# CDCEmu_Analog.net
KiCad netlist of a schematic drawn in EAGLE
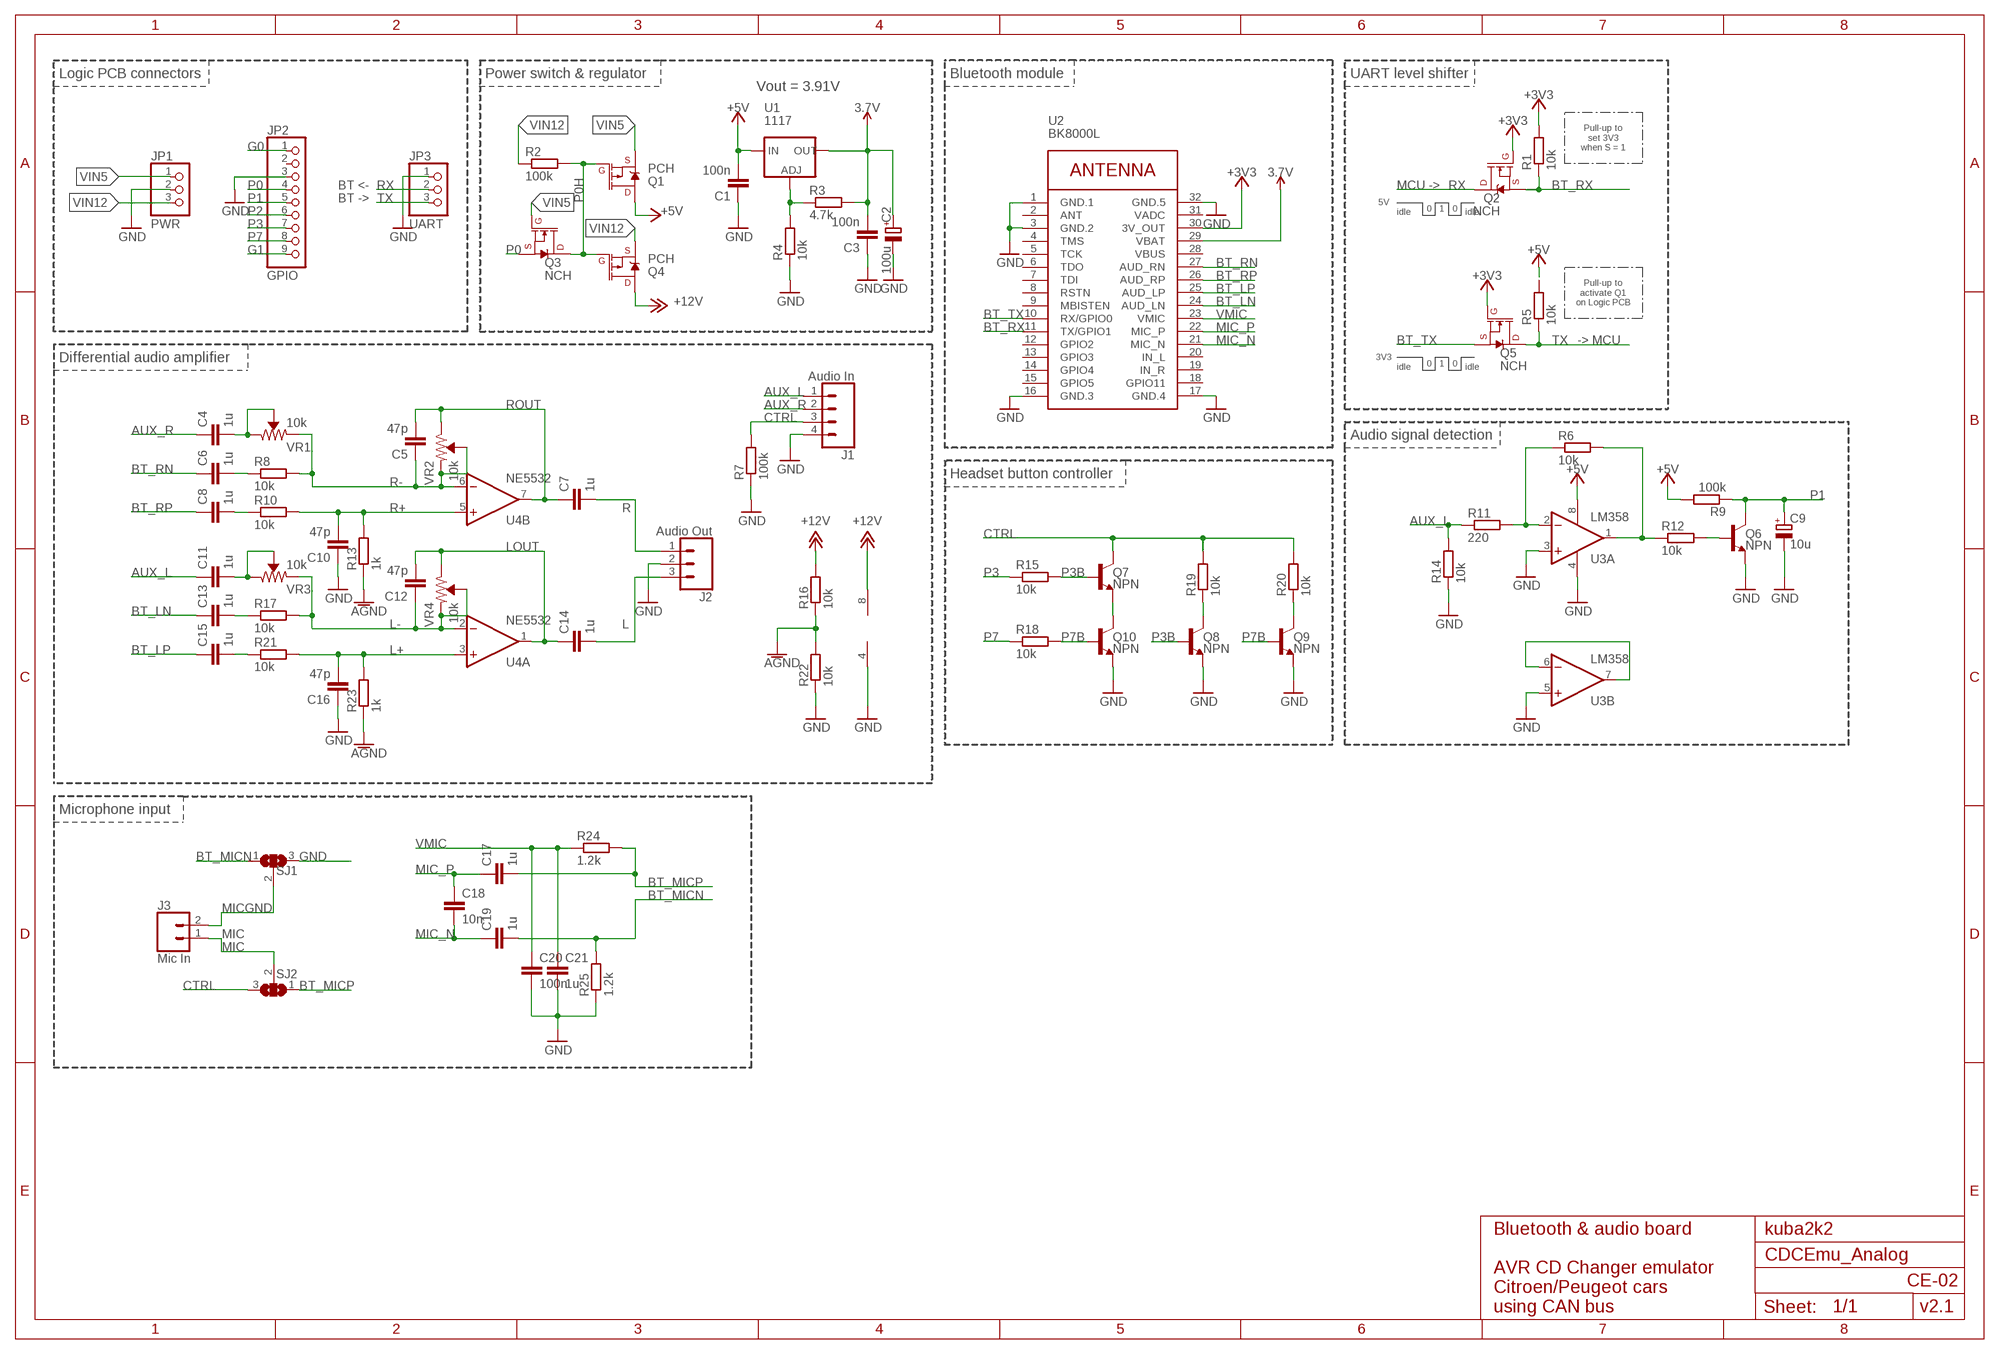
[diagram p0: schematic, sheet 1]

(export (version "E")
  (design (tool "Eeschema 10.0.6"))
  (components
    (comp (ref "C1")
      (value "100n")
      (footprint "eagle-import:C0805")
      (libsource (lib "eagle-import") (part "C-EUC0805"))
    )
    (comp (ref "C2")
      (value "100u")
      (footprint "eagle-import:SMC_B")
      (libsource (lib "eagle-import") (part "CPOL-EUSMCB"))
    )
    (comp (ref "C3")
      (value "100n")
      (footprint "eagle-import:C0805")
      (libsource (lib "eagle-import") (part "C-EUC0805"))
    )
    (comp (ref "C4")
      (value "1u")
      (footprint "eagle-import:C0805")
      (libsource (lib "eagle-import") (part "C-EUC0805"))
    )
    (comp (ref "C5")
      (value "47p")
      (footprint "eagle-import:C0805")
      (libsource (lib "eagle-import") (part "C-EUC0805"))
    )
    (comp (ref "C6")
      (value "1u")
      (footprint "eagle-import:C0805")
      (libsource (lib "eagle-import") (part "C-EUC0805"))
    )
    (comp (ref "C7")
      (value "1u")
      (footprint "eagle-import:C0805")
      (libsource (lib "eagle-import") (part "C-EUC0805"))
    )
    (comp (ref "C8")
      (value "1u")
      (footprint "eagle-import:C0805")
      (libsource (lib "eagle-import") (part "C-EUC0805"))
    )
    (comp (ref "C9")
      (value "10u")
      (footprint "eagle-import:C1206-POL")
      (libsource (lib "eagle-import") (part "CPOL-EUC1206"))
    )
    (comp (ref "C10")
      (value "47p")
      (footprint "eagle-import:C0805")
      (libsource (lib "eagle-import") (part "C-EUC0805"))
    )
    (comp (ref "C11")
      (value "1u")
      (footprint "eagle-import:C0805")
      (libsource (lib "eagle-import") (part "C-EUC0805"))
    )
    (comp (ref "C12")
      (value "47p")
      (footprint "eagle-import:C0805")
      (libsource (lib "eagle-import") (part "C-EUC0805"))
    )
    (comp (ref "C13")
      (value "1u")
      (footprint "eagle-import:C0805")
      (libsource (lib "eagle-import") (part "C-EUC0805"))
    )
    (comp (ref "C14")
      (value "1u")
      (footprint "eagle-import:C0805")
      (libsource (lib "eagle-import") (part "C-EUC0805"))
    )
    (comp (ref "C15")
      (value "1u")
      (footprint "eagle-import:C0805")
      (libsource (lib "eagle-import") (part "C-EUC0805"))
    )
    (comp (ref "C16")
      (value "47p")
      (footprint "eagle-import:C0805")
      (libsource (lib "eagle-import") (part "C-EUC0805"))
    )
    (comp (ref "C17")
      (value "1u")
      (footprint "eagle-import:C0805")
      (libsource (lib "eagle-import") (part "C-EUC0805"))
    )
    (comp (ref "C18")
      (value "10n")
      (footprint "eagle-import:C0805")
      (libsource (lib "eagle-import") (part "C-EUC0805"))
    )
    (comp (ref "C19")
      (value "1u")
      (footprint "eagle-import:C0805")
      (libsource (lib "eagle-import") (part "C-EUC0805"))
    )
    (comp (ref "C20")
      (value "100n")
      (footprint "eagle-import:C0805")
      (libsource (lib "eagle-import") (part "C-EUC0805"))
    )
    (comp (ref "C21")
      (value "1u")
      (footprint "eagle-import:C0805")
      (libsource (lib "eagle-import") (part "C-EUC0805"))
    )
    (comp (ref "J1")
      (value "Audio In")
      (footprint "eagle-import:JST-4-PTH")
      (libsource (lib "eagle-import") (part "CONN_04JST-PTH"))
    )
    (comp (ref "J2")
      (value "Audio Out")
      (footprint "eagle-import:JST-3-PTH")
      (libsource (lib "eagle-import") (part "CONN_03JST-PTH"))
    )
    (comp (ref "J3")
      (value "Mic In")
      (footprint "eagle-import:JST-2-PTH")
      (libsource (lib "eagle-import") (part "CONN_02JST-PTH-2"))
    )
    (comp (ref "JP1")
      (value "PWR")
      (footprint "eagle-import:1X03")
      (libsource (lib "eagle-import") (part "PINHD-1X3"))
    )
    (comp (ref "JP2")
      (value "GPIO")
      (footprint "eagle-import:1X09")
      (libsource (lib "eagle-import") (part "PINHD-1X9"))
    )
    (comp (ref "JP3")
      (value "UART")
      (footprint "eagle-import:1X03")
      (libsource (lib "eagle-import") (part "PINHD-1X3"))
    )
    (comp (ref "Q1")
      (value "PCH")
      (footprint "eagle-import:SOT23-3")
      (libsource (lib "eagle-import") (part "MOSFET_PCH-IRLML2244"))
    )
    (comp (ref "Q2")
      (value "NCH")
      (footprint "eagle-import:SOT23-3")
      (libsource (lib "eagle-import") (part "MOSFET-NCH-AO3404A"))
    )
    (comp (ref "Q3")
      (value "NCH")
      (footprint "eagle-import:SOT23-3")
      (libsource (lib "eagle-import") (part "MOSFET-NCH-AO3404A"))
    )
    (comp (ref "Q4")
      (value "PCH")
      (footprint "eagle-import:SOT23-3")
      (libsource (lib "eagle-import") (part "MOSFET_PCH-IRLML2244"))
    )
    (comp (ref "Q5")
      (value "NCH")
      (footprint "eagle-import:SOT23-3")
      (libsource (lib "eagle-import") (part "MOSFET-NCH-AO3404A"))
    )
    (comp (ref "Q6")
      (value "NPN")
      (footprint "eagle-import:SOT23-3")
      (libsource (lib "eagle-import") (part "TRANS_NPN-MMBTA42"))
    )
    (comp (ref "Q7")
      (value "NPN")
      (footprint "eagle-import:SOT23-3")
      (libsource (lib "eagle-import") (part "TRANS_NPN-MMBTA42"))
    )
    (comp (ref "Q8")
      (value "NPN")
      (footprint "eagle-import:SOT23-3")
      (libsource (lib "eagle-import") (part "TRANS_NPN-MMBTA42"))
    )
    (comp (ref "Q9")
      (value "NPN")
      (footprint "eagle-import:SOT23-3")
      (libsource (lib "eagle-import") (part "TRANS_NPN-MMBTA42"))
    )
    (comp (ref "Q10")
      (value "NPN")
      (footprint "eagle-import:SOT23-3")
      (libsource (lib "eagle-import") (part "TRANS_NPN-MMBTA42"))
    )
    (comp (ref "R1")
      (value "10k")
      (footprint "eagle-import:R0805")
      (libsource (lib "eagle-import") (part "R-EU_R0805"))
    )
    (comp (ref "R2")
      (value "100k")
      (footprint "eagle-import:R0805")
      (libsource (lib "eagle-import") (part "R-EU_R0805"))
    )
    (comp (ref "R3")
      (value "4.7k")
      (footprint "eagle-import:R0805")
      (libsource (lib "eagle-import") (part "R-EU_R0805"))
    )
    (comp (ref "R4")
      (value "10k")
      (footprint "eagle-import:R0805")
      (libsource (lib "eagle-import") (part "R-EU_R0805"))
    )
    (comp (ref "R5")
      (value "10k")
      (footprint "eagle-import:R0805")
      (libsource (lib "eagle-import") (part "R-EU_R0805"))
    )
    (comp (ref "R6")
      (value "10k")
      (footprint "eagle-import:R0805")
      (libsource (lib "eagle-import") (part "R-EU_R0805"))
    )
    (comp (ref "R7")
      (value "100k")
      (footprint "eagle-import:R0805")
      (libsource (lib "eagle-import") (part "R-EU_R0805"))
    )
    (comp (ref "R8")
      (value "10k")
      (footprint "eagle-import:R0805")
      (libsource (lib "eagle-import") (part "R-EU_R0805"))
    )
    (comp (ref "R9")
      (value "100k")
      (footprint "eagle-import:R0805")
      (libsource (lib "eagle-import") (part "R-EU_R0805"))
    )
    (comp (ref "R10")
      (value "10k")
      (footprint "eagle-import:R0805")
      (libsource (lib "eagle-import") (part "R-EU_R0805"))
    )
    (comp (ref "R11")
      (value "220")
      (footprint "eagle-import:R0805")
      (libsource (lib "eagle-import") (part "R-EU_R0805"))
    )
    (comp (ref "R12")
      (value "10k")
      (footprint "eagle-import:R0805")
      (libsource (lib "eagle-import") (part "R-EU_R0805"))
    )
    (comp (ref "R13")
      (value "1k")
      (footprint "eagle-import:R0805")
      (libsource (lib "eagle-import") (part "R-EU_R0805"))
    )
    (comp (ref "R14")
      (value "10k")
      (footprint "eagle-import:R0805")
      (libsource (lib "eagle-import") (part "R-EU_R0805"))
    )
    (comp (ref "R15")
      (value "10k")
      (footprint "eagle-import:R0805")
      (libsource (lib "eagle-import") (part "R-EU_R0805"))
    )
    (comp (ref "R16")
      (value "10k")
      (footprint "eagle-import:R0805")
      (libsource (lib "eagle-import") (part "R-EU_R0805"))
    )
    (comp (ref "R17")
      (value "10k")
      (footprint "eagle-import:R0805")
      (libsource (lib "eagle-import") (part "R-EU_R0805"))
    )
    (comp (ref "R18")
      (value "10k")
      (footprint "eagle-import:R0805")
      (libsource (lib "eagle-import") (part "R-EU_R0805"))
    )
    (comp (ref "R19")
      (value "10k")
      (footprint "eagle-import:R0805")
      (libsource (lib "eagle-import") (part "R-EU_R0805"))
    )
    (comp (ref "R20")
      (value "10k")
      (footprint "eagle-import:R0805")
      (libsource (lib "eagle-import") (part "R-EU_R0805"))
    )
    (comp (ref "R21")
      (value "10k")
      (footprint "eagle-import:R0805")
      (libsource (lib "eagle-import") (part "R-EU_R0805"))
    )
    (comp (ref "R22")
      (value "10k")
      (footprint "eagle-import:R0805")
      (libsource (lib "eagle-import") (part "R-EU_R0805"))
    )
    (comp (ref "R23")
      (value "1k")
      (footprint "eagle-import:R0805")
      (libsource (lib "eagle-import") (part "R-EU_R0805"))
    )
    (comp (ref "R24")
      (value "1.2k")
      (footprint "eagle-import:R0805")
      (libsource (lib "eagle-import") (part "R-EU_R0805"))
    )
    (comp (ref "R25")
      (value "1.2k")
      (footprint "eagle-import:R0805")
      (libsource (lib "eagle-import") (part "R-EU_R0805"))
    )
    (comp (ref "SJ1")
      (value "SJ2W")
      (footprint "eagle-import:SJ_2")
      (libsource (lib "eagle-import") (part "SJ2W"))
    )
    (comp (ref "SJ2")
      (value "SJ2W")
      (footprint "eagle-import:SJ_2")
      (libsource (lib "eagle-import") (part "SJ2W"))
    )
    (comp (ref "U1")
      (value "1117")
      (footprint "eagle-import:SOT223")
      (libsource (lib "eagle-import") (part "V_REG_LM1117SOT223"))
    )
    (comp (ref "U2")
      (value "BK8000L")
      (footprint "eagle-import:WIRELESS-BLUETOOTH-BK8000")
      (libsource (lib "eagle-import") (part "WIRELESS-BLUETOOTH-BK8000"))
    )
    (comp (ref "U3")
      (value "LM358")
      (footprint "eagle-import:SO08")
      (libsource (lib "eagle-import") (part "LM358D"))
    )
    (comp (ref "U4")
      (value "NE5532")
      (footprint "eagle-import:SO08")
      (libsource (lib "eagle-import") (part "LM358D"))
    )
    (comp (ref "VR1")
      (value "10k")
      (footprint "eagle-import:TRIMPOT-SMD-TC33X")
      (libsource (lib "eagle-import") (part "TRIMPOT-SMD-3MM-OPEN-1/10W-25%"))
    )
    (comp (ref "VR2")
      (value "10k")
      (footprint "eagle-import:TRIMPOT-SMD-TC33X")
      (libsource (lib "eagle-import") (part "TRIMPOT-SMD-3MM-OPEN-1/10W-25%"))
    )
    (comp (ref "VR3")
      (value "10k")
      (footprint "eagle-import:TRIMPOT-SMD-TC33X")
      (libsource (lib "eagle-import") (part "TRIMPOT-SMD-3MM-OPEN-1/10W-25%"))
    )
    (comp (ref "VR4")
      (value "10k")
      (footprint "eagle-import:TRIMPOT-SMD-TC33X")
      (libsource (lib "eagle-import") (part "TRIMPOT-SMD-3MM-OPEN-1/10W-25%"))
    )
  )
  (nets
    (net (code "1") (name "+3V3") (class "Default")
      (node (ref "Q2") (pin "1") (pinfunction "G_1") (pintype "bidirectional"))
      (node (ref "Q5") (pin "1") (pinfunction "G_1") (pintype "bidirectional"))
      (node (ref "R1") (pin "2") (pinfunction "2_2") (pintype "passive"))
      (node (ref "U2") (pin "30") (pinfunction "3V_OUT_30") (pintype "power_in"))
    )
    (net (code "2") (name "+5V") (class "Default")
      (node (ref "C1") (pin "2") (pinfunction "2_2") (pintype "passive"))
      (node (ref "Q1") (pin "3") (pinfunction "D_3") (pintype "bidirectional"))
      (node (ref "R5") (pin "2") (pinfunction "2_2") (pintype "passive"))
      (node (ref "R9") (pin "2") (pinfunction "2_2") (pintype "passive"))
      (node (ref "U1") (pin "3") (pinfunction "IN_3") (pintype "input"))
      (node (ref "U3") (pin "8") (pinfunction "V+_8") (pintype "power_in"))
    )
    (net (code "3") (name "+12V") (class "Default")
      (node (ref "Q4") (pin "3") (pinfunction "D_3") (pintype "bidirectional"))
      (node (ref "R16") (pin "2") (pinfunction "2_2") (pintype "passive"))
      (node (ref "U4") (pin "8") (pinfunction "V+_8") (pintype "power_in"))
    )
    (net (code "4") (name "/AUX_L") (class "Default")
      (node (ref "C11") (pin "1") (pinfunction "1_1") (pintype "passive"))
      (node (ref "J1") (pin "1") (pinfunction "1_1") (pintype "passive"))
      (node (ref "R11") (pin "1") (pinfunction "1_1") (pintype "passive"))
      (node (ref "R14") (pin "2") (pinfunction "2_2") (pintype "passive"))
    )
    (net (code "5") (name "/AUX_R") (class "Default")
      (node (ref "C4") (pin "1") (pinfunction "1_1") (pintype "passive"))
      (node (ref "J1") (pin "2") (pinfunction "2_2") (pintype "passive"))
    )
    (net (code "6") (name "/BT_LN") (class "Default")
      (node (ref "C13") (pin "1") (pinfunction "1_1") (pintype "passive"))
      (node (ref "U2") (pin "24") (pinfunction "AUD_LN_24") (pintype "output"))
    )
    (net (code "7") (name "/BT_LP") (class "Default")
      (node (ref "C15") (pin "1") (pinfunction "1_1") (pintype "passive"))
      (node (ref "U2") (pin "25") (pinfunction "AUD_LP_25") (pintype "output"))
    )
    (net (code "8") (name "/BT_MICN") (class "Default")
      (node (ref "C19") (pin "2") (pinfunction "2_2") (pintype "passive"))
      (node (ref "R25") (pin "2") (pinfunction "2_2") (pintype "passive"))
      (node (ref "SJ1") (pin "1") (pinfunction "1_1") (pintype "passive"))
    )
    (net (code "9") (name "/BT_MICP") (class "Default")
      (node (ref "C17") (pin "2") (pinfunction "2_2") (pintype "passive"))
      (node (ref "R24") (pin "2") (pinfunction "2_2") (pintype "passive"))
      (node (ref "SJ2") (pin "1") (pinfunction "1_1") (pintype "passive"))
    )
    (net (code "10") (name "/BT_RN") (class "Default")
      (node (ref "C6") (pin "1") (pinfunction "1_1") (pintype "passive"))
      (node (ref "U2") (pin "27") (pinfunction "AUD_RN_27") (pintype "output"))
    )
    (net (code "11") (name "/BT_RP") (class "Default")
      (node (ref "C8") (pin "1") (pinfunction "1_1") (pintype "passive"))
      (node (ref "U2") (pin "26") (pinfunction "AUD_RP_26") (pintype "output"))
    )
    (net (code "12") (name "/BT_RX") (class "Default")
      (node (ref "Q2") (pin "2") (pinfunction "S_2") (pintype "bidirectional"))
      (node (ref "R1") (pin "1") (pinfunction "1_1") (pintype "passive"))
      (node (ref "U2") (pin "11") (pinfunction "TX/GPIO1_11") (pintype "bidirectional"))
    )
    (net (code "13") (name "/BT_TX") (class "Default")
      (node (ref "Q5") (pin "2") (pinfunction "S_2") (pintype "bidirectional"))
      (node (ref "U2") (pin "10") (pinfunction "RX/GPIO0_10") (pintype "bidirectional"))
    )
    (net (code "14") (name "/CTRL") (class "Default")
      (node (ref "J1") (pin "3") (pinfunction "3_3") (pintype "passive"))
      (node (ref "Q7") (pin "3") (pinfunction "C_3") (pintype "passive"))
      (node (ref "R19") (pin "2") (pinfunction "2_2") (pintype "passive"))
      (node (ref "R20") (pin "2") (pinfunction "2_2") (pintype "passive"))
      (node (ref "R7") (pin "2") (pinfunction "2_2") (pintype "passive"))
      (node (ref "SJ2") (pin "3") (pinfunction "3_3") (pintype "passive"))
    )
    (net (code "15") (name "/G0") (class "Default")
      (node (ref "JP2") (pin "1") (pinfunction "1_1") (pintype "passive"))
    )
    (net (code "16") (name "/G1") (class "Default")
      (node (ref "JP2") (pin "9") (pinfunction "9_9") (pintype "passive"))
    )
    (net (code "17") (name "/L") (class "Default")
      (node (ref "C14") (pin "2") (pinfunction "2_2") (pintype "passive"))
      (node (ref "J2") (pin "3") (pinfunction "3_3") (pintype "passive"))
    )
    (net (code "18") (name "/L+") (class "Default")
      (node (ref "C16") (pin "2") (pinfunction "2_2") (pintype "passive"))
      (node (ref "R21") (pin "2") (pinfunction "2_2") (pintype "passive"))
      (node (ref "R23") (pin "2") (pinfunction "2_2") (pintype "passive"))
      (node (ref "U4") (pin "3") (pinfunction "+IN_3") (pintype "input"))
    )
    (net (code "19") (name "/L-") (class "Default")
      (node (ref "C12") (pin "1") (pinfunction "1_1") (pintype "passive"))
      (node (ref "R17") (pin "2") (pinfunction "2_2") (pintype "passive"))
      (node (ref "U4") (pin "2") (pinfunction "-IN_2") (pintype "input"))
      (node (ref "VR3") (pin "3") (pinfunction "CCW_3") (pintype "passive"))
      (node (ref "VR4") (pin "2") (pinfunction "WIPER_2") (pintype "passive"))
      (node (ref "VR4") (pin "3") (pinfunction "CCW_3") (pintype "passive"))
    )
    (net (code "20") (name "/LOUT") (class "Default")
      (node (ref "C12") (pin "2") (pinfunction "2_2") (pintype "passive"))
      (node (ref "C14") (pin "1") (pinfunction "1_1") (pintype "passive"))
      (node (ref "U4") (pin "1") (pinfunction "OUT_1") (pintype "output"))
      (node (ref "VR4") (pin "1") (pinfunction "CW_1") (pintype "passive"))
    )
    (net (code "21") (name "/MIC") (class "Default")
      (node (ref "J3") (pin "1") (pinfunction "1_1") (pintype "passive"))
      (node (ref "SJ2") (pin "2") (pinfunction "2_2") (pintype "passive"))
    )
    (net (code "22") (name "/MICGND") (class "Default")
      (node (ref "J3") (pin "2") (pinfunction "2_2") (pintype "passive"))
      (node (ref "SJ1") (pin "2") (pinfunction "2_2") (pintype "passive"))
    )
    (net (code "23") (name "/MIC_N") (class "Default")
      (node (ref "C18") (pin "2") (pinfunction "2_2") (pintype "passive"))
      (node (ref "C19") (pin "1") (pinfunction "1_1") (pintype "passive"))
      (node (ref "U2") (pin "21") (pinfunction "MIC_N_21") (pintype "input"))
    )
    (net (code "24") (name "/MIC_P") (class "Default")
      (node (ref "C17") (pin "1") (pinfunction "1_1") (pintype "passive"))
      (node (ref "C18") (pin "1") (pinfunction "1_1") (pintype "passive"))
      (node (ref "U2") (pin "22") (pinfunction "MIC_P_22") (pintype "input"))
    )
    (net (code "25") (name "/P0") (class "Default")
      (node (ref "JP2") (pin "4") (pinfunction "4_4") (pintype "passive"))
      (node (ref "Q3") (pin "2") (pinfunction "S_2") (pintype "bidirectional"))
    )
    (net (code "26") (name "/P0H") (class "Default")
      (node (ref "Q1") (pin "1") (pinfunction "G_1") (pintype "bidirectional"))
      (node (ref "Q3") (pin "3") (pinfunction "D_3") (pintype "bidirectional"))
      (node (ref "Q4") (pin "1") (pinfunction "G_1") (pintype "bidirectional"))
      (node (ref "R2") (pin "2") (pinfunction "2_2") (pintype "passive"))
    )
    (net (code "27") (name "/P1") (class "Default")
      (node (ref "C9") (pin "1") (pinfunction "+_1") (pintype "passive"))
      (node (ref "JP2") (pin "5") (pinfunction "5_5") (pintype "passive"))
      (node (ref "Q6") (pin "3") (pinfunction "C_3") (pintype "passive"))
      (node (ref "R9") (pin "1") (pinfunction "1_1") (pintype "passive"))
    )
    (net (code "28") (name "/P2") (class "Default")
      (node (ref "JP2") (pin "6") (pinfunction "6_6") (pintype "passive"))
    )
    (net (code "29") (name "/P3") (class "Default")
      (node (ref "JP2") (pin "7") (pinfunction "7_7") (pintype "passive"))
      (node (ref "R15") (pin "1") (pinfunction "1_1") (pintype "passive"))
    )
    (net (code "30") (name "/P3B") (class "Default")
      (node (ref "Q7") (pin "1") (pinfunction "B_1") (pintype "passive"))
      (node (ref "Q8") (pin "1") (pinfunction "B_1") (pintype "passive"))
      (node (ref "R15") (pin "2") (pinfunction "2_2") (pintype "passive"))
    )
    (net (code "31") (name "/P7") (class "Default")
      (node (ref "JP2") (pin "8") (pinfunction "8_8") (pintype "passive"))
      (node (ref "R18") (pin "1") (pinfunction "1_1") (pintype "passive"))
    )
    (net (code "32") (name "/P7B") (class "Default")
      (node (ref "Q10") (pin "1") (pinfunction "B_1") (pintype "passive"))
      (node (ref "Q9") (pin "1") (pinfunction "B_1") (pintype "passive"))
      (node (ref "R18") (pin "2") (pinfunction "2_2") (pintype "passive"))
    )
    (net (code "33") (name "/R") (class "Default")
      (node (ref "C7") (pin "2") (pinfunction "2_2") (pintype "passive"))
      (node (ref "J2") (pin "1") (pinfunction "1_1") (pintype "passive"))
    )
    (net (code "34") (name "/R+") (class "Default")
      (node (ref "C10") (pin "2") (pinfunction "2_2") (pintype "passive"))
      (node (ref "R10") (pin "2") (pinfunction "2_2") (pintype "passive"))
      (node (ref "R13") (pin "2") (pinfunction "2_2") (pintype "passive"))
      (node (ref "U4") (pin "5") (pinfunction "+IN_5") (pintype "input"))
    )
    (net (code "35") (name "/R-") (class "Default")
      (node (ref "C5") (pin "1") (pinfunction "1_1") (pintype "passive"))
      (node (ref "R8") (pin "2") (pinfunction "2_2") (pintype "passive"))
      (node (ref "U4") (pin "6") (pinfunction "-IN_6") (pintype "input"))
      (node (ref "VR1") (pin "3") (pinfunction "CCW_3") (pintype "passive"))
      (node (ref "VR2") (pin "2") (pinfunction "WIPER_2") (pintype "passive"))
      (node (ref "VR2") (pin "3") (pinfunction "CCW_3") (pintype "passive"))
    )
    (net (code "36") (name "/ROUT") (class "Default")
      (node (ref "C5") (pin "2") (pinfunction "2_2") (pintype "passive"))
      (node (ref "C7") (pin "1") (pinfunction "1_1") (pintype "passive"))
      (node (ref "U4") (pin "7") (pinfunction "OUT_7") (pintype "output"))
      (node (ref "VR2") (pin "1") (pinfunction "CW_1") (pintype "passive"))
    )
    (net (code "37") (name "/RX") (class "Default")
      (node (ref "JP3") (pin "2") (pinfunction "2_2") (pintype "passive"))
      (node (ref "Q2") (pin "3") (pinfunction "D_3") (pintype "bidirectional"))
    )
    (net (code "38") (name "/TX") (class "Default")
      (node (ref "JP3") (pin "3") (pinfunction "3_3") (pintype "passive"))
      (node (ref "Q5") (pin "3") (pinfunction "D_3") (pintype "bidirectional"))
      (node (ref "R5") (pin "1") (pinfunction "1_1") (pintype "passive"))
    )
    (net (code "39") (name "/VADC") (class "Default")
      (node (ref "U2") (pin "31") (pinfunction "VADC_31") (pintype "power_in"))
    )
    (net (code "40") (name "/VMIC") (class "Default")
      (node (ref "C20") (pin "1") (pinfunction "1_1") (pintype "passive"))
      (node (ref "C21") (pin "1") (pinfunction "1_1") (pintype "passive"))
      (node (ref "R24") (pin "1") (pinfunction "1_1") (pintype "passive"))
      (node (ref "U2") (pin "23") (pinfunction "VMIC_23") (pintype "passive"))
    )
    (net (code "41") (name "3.7V") (class "Default")
      (node (ref "C2") (pin "+") (pinfunction "+_+") (pintype "passive"))
      (node (ref "C3") (pin "2") (pinfunction "2_2") (pintype "passive"))
      (node (ref "R3") (pin "2") (pinfunction "2_2") (pintype "passive"))
      (node (ref "U1") (pin "2") (pinfunction "OUT_2") (pintype "output"))
      (node (ref "U1") (pin "4") (pinfunction "OUT_4") (pintype "output"))
      (node (ref "U2") (pin "29") (pinfunction "VBAT_29") (pintype "passive"))
    )
    (net (code "42") (name "AGND") (class "Default")
      (node (ref "R13") (pin "1") (pinfunction "1_1") (pintype "passive"))
      (node (ref "R16") (pin "1") (pinfunction "1_1") (pintype "passive"))
      (node (ref "R22") (pin "2") (pinfunction "2_2") (pintype "passive"))
      (node (ref "R23") (pin "1") (pinfunction "1_1") (pintype "passive"))
    )
    (net (code "43") (name "GND") (class "Default")
      (node (ref "C1") (pin "1") (pinfunction "1_1") (pintype "passive"))
      (node (ref "C10") (pin "1") (pinfunction "1_1") (pintype "passive"))
      (node (ref "C16") (pin "1") (pinfunction "1_1") (pintype "passive"))
      (node (ref "C2") (pin "-") (pinfunction "-_-") (pintype "passive"))
      (node (ref "C20") (pin "2") (pinfunction "2_2") (pintype "passive"))
      (node (ref "C21") (pin "2") (pinfunction "2_2") (pintype "passive"))
      (node (ref "C3") (pin "1") (pinfunction "1_1") (pintype "passive"))
      (node (ref "C9") (pin "2") (pinfunction "-_2") (pintype "passive"))
      (node (ref "J1") (pin "4") (pinfunction "4_4") (pintype "passive"))
      (node (ref "J2") (pin "2") (pinfunction "2_2") (pintype "passive"))
      (node (ref "JP1") (pin "2") (pinfunction "2_2") (pintype "passive"))
      (node (ref "JP2") (pin "3") (pinfunction "3_3") (pintype "passive"))
      (node (ref "JP3") (pin "1") (pinfunction "1_1") (pintype "passive"))
      (node (ref "Q10") (pin "2") (pinfunction "E_2") (pintype "passive"))
      (node (ref "Q6") (pin "2") (pinfunction "E_2") (pintype "passive"))
      (node (ref "Q8") (pin "2") (pinfunction "E_2") (pintype "passive"))
      (node (ref "Q9") (pin "2") (pinfunction "E_2") (pintype "passive"))
      (node (ref "R14") (pin "1") (pinfunction "1_1") (pintype "passive"))
      (node (ref "R22") (pin "1") (pinfunction "1_1") (pintype "passive"))
      (node (ref "R25") (pin "1") (pinfunction "1_1") (pintype "passive"))
      (node (ref "R4") (pin "1") (pinfunction "1_1") (pintype "passive"))
      (node (ref "R7") (pin "1") (pinfunction "1_1") (pintype "passive"))
      (node (ref "SJ1") (pin "3") (pinfunction "3_3") (pintype "passive"))
      (node (ref "U2") (pin "1") (pinfunction "GND.1_1") (pintype "power_in"))
      (node (ref "U2") (pin "16") (pinfunction "GND.3_16") (pintype "power_in"))
      (node (ref "U2") (pin "17") (pinfunction "GND.4_17") (pintype "power_in"))
      (node (ref "U2") (pin "3") (pinfunction "GND.2_3") (pintype "power_in"))
      (node (ref "U2") (pin "32") (pinfunction "GND.5_32") (pintype "power_in"))
      (node (ref "U3") (pin "3") (pinfunction "+IN_3") (pintype "input"))
      (node (ref "U3") (pin "4") (pinfunction "V-_4") (pintype "power_in"))
      (node (ref "U3") (pin "5") (pinfunction "+IN_5") (pintype "input"))
      (node (ref "U4") (pin "4") (pinfunction "V-_4") (pintype "power_in"))
    )
    (net (code "44") (name "Net-(C6-Pad2)") (class "Default")
      (node (ref "C6") (pin "2") (pinfunction "2_2") (pintype "passive"))
      (node (ref "R8") (pin "1") (pinfunction "1_1") (pintype "passive"))
    )
    (net (code "45") (name "Net-(C8-Pad2)") (class "Default")
      (node (ref "C8") (pin "2") (pinfunction "2_2") (pintype "passive"))
      (node (ref "R10") (pin "1") (pinfunction "1_1") (pintype "passive"))
    )
    (net (code "46") (name "Net-(C13-Pad2)") (class "Default")
      (node (ref "C13") (pin "2") (pinfunction "2_2") (pintype "passive"))
      (node (ref "R17") (pin "1") (pinfunction "1_1") (pintype "passive"))
    )
    (net (code "47") (name "Net-(C15-Pad2)") (class "Default")
      (node (ref "C15") (pin "2") (pinfunction "2_2") (pintype "passive"))
      (node (ref "R21") (pin "1") (pinfunction "1_1") (pintype "passive"))
    )
    (net (code "48") (name "Net-(Q6-B)") (class "Default")
      (node (ref "Q6") (pin "1") (pinfunction "B_1") (pintype "passive"))
      (node (ref "R12") (pin "2") (pinfunction "2_2") (pintype "passive"))
    )
    (net (code "49") (name "Net-(Q8-C)") (class "Default")
      (node (ref "Q8") (pin "3") (pinfunction "C_3") (pintype "passive"))
      (node (ref "R19") (pin "1") (pinfunction "1_1") (pintype "passive"))
    )
    (net (code "50") (name "Net-(Q9-C)") (class "Default")
      (node (ref "Q9") (pin "3") (pinfunction "C_3") (pintype "passive"))
      (node (ref "R20") (pin "1") (pinfunction "1_1") (pintype "passive"))
    )
    (net (code "51") (name "Net-(Q10-C)") (class "Default")
      (node (ref "Q10") (pin "3") (pinfunction "C_3") (pintype "passive"))
      (node (ref "Q7") (pin "2") (pinfunction "E_2") (pintype "passive"))
    )
    (net (code "52") (name "Net-(U1-ADJ)") (class "Default")
      (node (ref "R3") (pin "1") (pinfunction "1_1") (pintype "passive"))
      (node (ref "R4") (pin "2") (pinfunction "2_2") (pintype "passive"))
      (node (ref "U1") (pin "1") (pinfunction "ADJ_1") (pintype "input"))
    )
    (net (code "53") (name "Net-(U3A--IN)") (class "Default")
      (node (ref "R11") (pin "2") (pinfunction "2_2") (pintype "passive"))
      (node (ref "R6") (pin "1") (pinfunction "1_1") (pintype "passive"))
      (node (ref "U3") (pin "2") (pinfunction "-IN_2") (pintype "input"))
    )
    (net (code "54") (name "Net-(U3A-OUT)") (class "Default")
      (node (ref "R12") (pin "1") (pinfunction "1_1") (pintype "passive"))
      (node (ref "R6") (pin "2") (pinfunction "2_2") (pintype "passive"))
      (node (ref "U3") (pin "1") (pinfunction "OUT_1") (pintype "output"))
    )
    (net (code "55") (name "Net-(U3B--IN)") (class "Default")
      (node (ref "U3") (pin "6") (pinfunction "-IN_6") (pintype "input"))
      (node (ref "U3") (pin "7") (pinfunction "OUT_7") (pintype "output"))
    )
    (net (code "56") (name "Net-(VR1-CW)") (class "Default")
      (node (ref "C4") (pin "2") (pinfunction "2_2") (pintype "passive"))
      (node (ref "VR1") (pin "1") (pinfunction "CW_1") (pintype "passive"))
      (node (ref "VR1") (pin "2") (pinfunction "WIPER_2") (pintype "passive"))
    )
    (net (code "57") (name "Net-(VR3-CW)") (class "Default")
      (node (ref "C11") (pin "2") (pinfunction "2_2") (pintype "passive"))
      (node (ref "VR3") (pin "1") (pinfunction "CW_1") (pintype "passive"))
      (node (ref "VR3") (pin "2") (pinfunction "WIPER_2") (pintype "passive"))
    )
    (net (code "58") (name "VIN5") (class "Default")
      (node (ref "JP1") (pin "1") (pinfunction "1_1") (pintype "passive"))
      (node (ref "Q1") (pin "2") (pinfunction "S_2") (pintype "bidirectional"))
      (node (ref "Q3") (pin "1") (pinfunction "G_1") (pintype "bidirectional"))
    )
    (net (code "59") (name "VIN12") (class "Default")
      (node (ref "JP1") (pin "3") (pinfunction "3_3") (pintype "passive"))
      (node (ref "Q4") (pin "2") (pinfunction "S_2") (pintype "bidirectional"))
      (node (ref "R2") (pin "1") (pinfunction "1_1") (pintype "passive"))
    )
    (net (code "60") (name "unconnected-(JP2-Pad2)") (class "Default")
      (node (ref "JP2") (pin "2") (pinfunction "2_2") (pintype "passive"))
    )
    (net (code "61") (name "unconnected-(U2-ANT-Pad2)") (class "Default")
      (node (ref "U2") (pin "2") (pinfunction "ANT_2") (pintype "passive"))
    )
    (net (code "62") (name "unconnected-(U2-GPIO2-Pad12)") (class "Default")
      (node (ref "U2") (pin "12") (pinfunction "GPIO2_12") (pintype "bidirectional"))
    )
    (net (code "63") (name "unconnected-(U2-GPIO3-Pad13)") (class "Default")
      (node (ref "U2") (pin "13") (pinfunction "GPIO3_13") (pintype "bidirectional"))
    )
    (net (code "64") (name "unconnected-(U2-GPIO4-Pad14)") (class "Default")
      (node (ref "U2") (pin "14") (pinfunction "GPIO4_14") (pintype "bidirectional"))
    )
    (net (code "65") (name "unconnected-(U2-GPIO5-Pad15)") (class "Default")
      (node (ref "U2") (pin "15") (pinfunction "GPIO5_15") (pintype "bidirectional"))
    )
    (net (code "66") (name "unconnected-(U2-GPIO11-Pad18)") (class "Default")
      (node (ref "U2") (pin "18") (pinfunction "GPIO11_18") (pintype "bidirectional"))
    )
    (net (code "67") (name "unconnected-(U2-IN_L-Pad20)") (class "Default")
      (node (ref "U2") (pin "20") (pinfunction "IN_L_20") (pintype "input"))
    )
    (net (code "68") (name "unconnected-(U2-IN_R-Pad19)") (class "Default")
      (node (ref "U2") (pin "19") (pinfunction "IN_R_19") (pintype "input"))
    )
    (net (code "69") (name "unconnected-(U2-MBISTEN-Pad9)") (class "Default")
      (node (ref "U2") (pin "9") (pinfunction "MBISTEN_9") (pintype "bidirectional"))
    )
    (net (code "70") (name "unconnected-(U2-RSTN-Pad8)") (class "Default")
      (node (ref "U2") (pin "8") (pinfunction "RSTN_8") (pintype "bidirectional"))
    )
    (net (code "71") (name "unconnected-(U2-TCK-Pad5)") (class "Default")
      (node (ref "U2") (pin "5") (pinfunction "TCK_5") (pintype "bidirectional"))
    )
    (net (code "72") (name "unconnected-(U2-TDI-Pad7)") (class "Default")
      (node (ref "U2") (pin "7") (pinfunction "TDI_7") (pintype "bidirectional"))
    )
    (net (code "73") (name "unconnected-(U2-TDO-Pad6)") (class "Default")
      (node (ref "U2") (pin "6") (pinfunction "TDO_6") (pintype "bidirectional"))
    )
    (net (code "74") (name "unconnected-(U2-TMS-Pad4)") (class "Default")
      (node (ref "U2") (pin "4") (pinfunction "TMS_4") (pintype "bidirectional"))
    )
    (net (code "75") (name "unconnected-(U2-VBUS-Pad28)") (class "Default")
      (node (ref "U2") (pin "28") (pinfunction "VBUS_28") (pintype "passive"))
    )
  )
)
